# DFTT.net
KiCad netlist of a schematic drawn in EAGLE
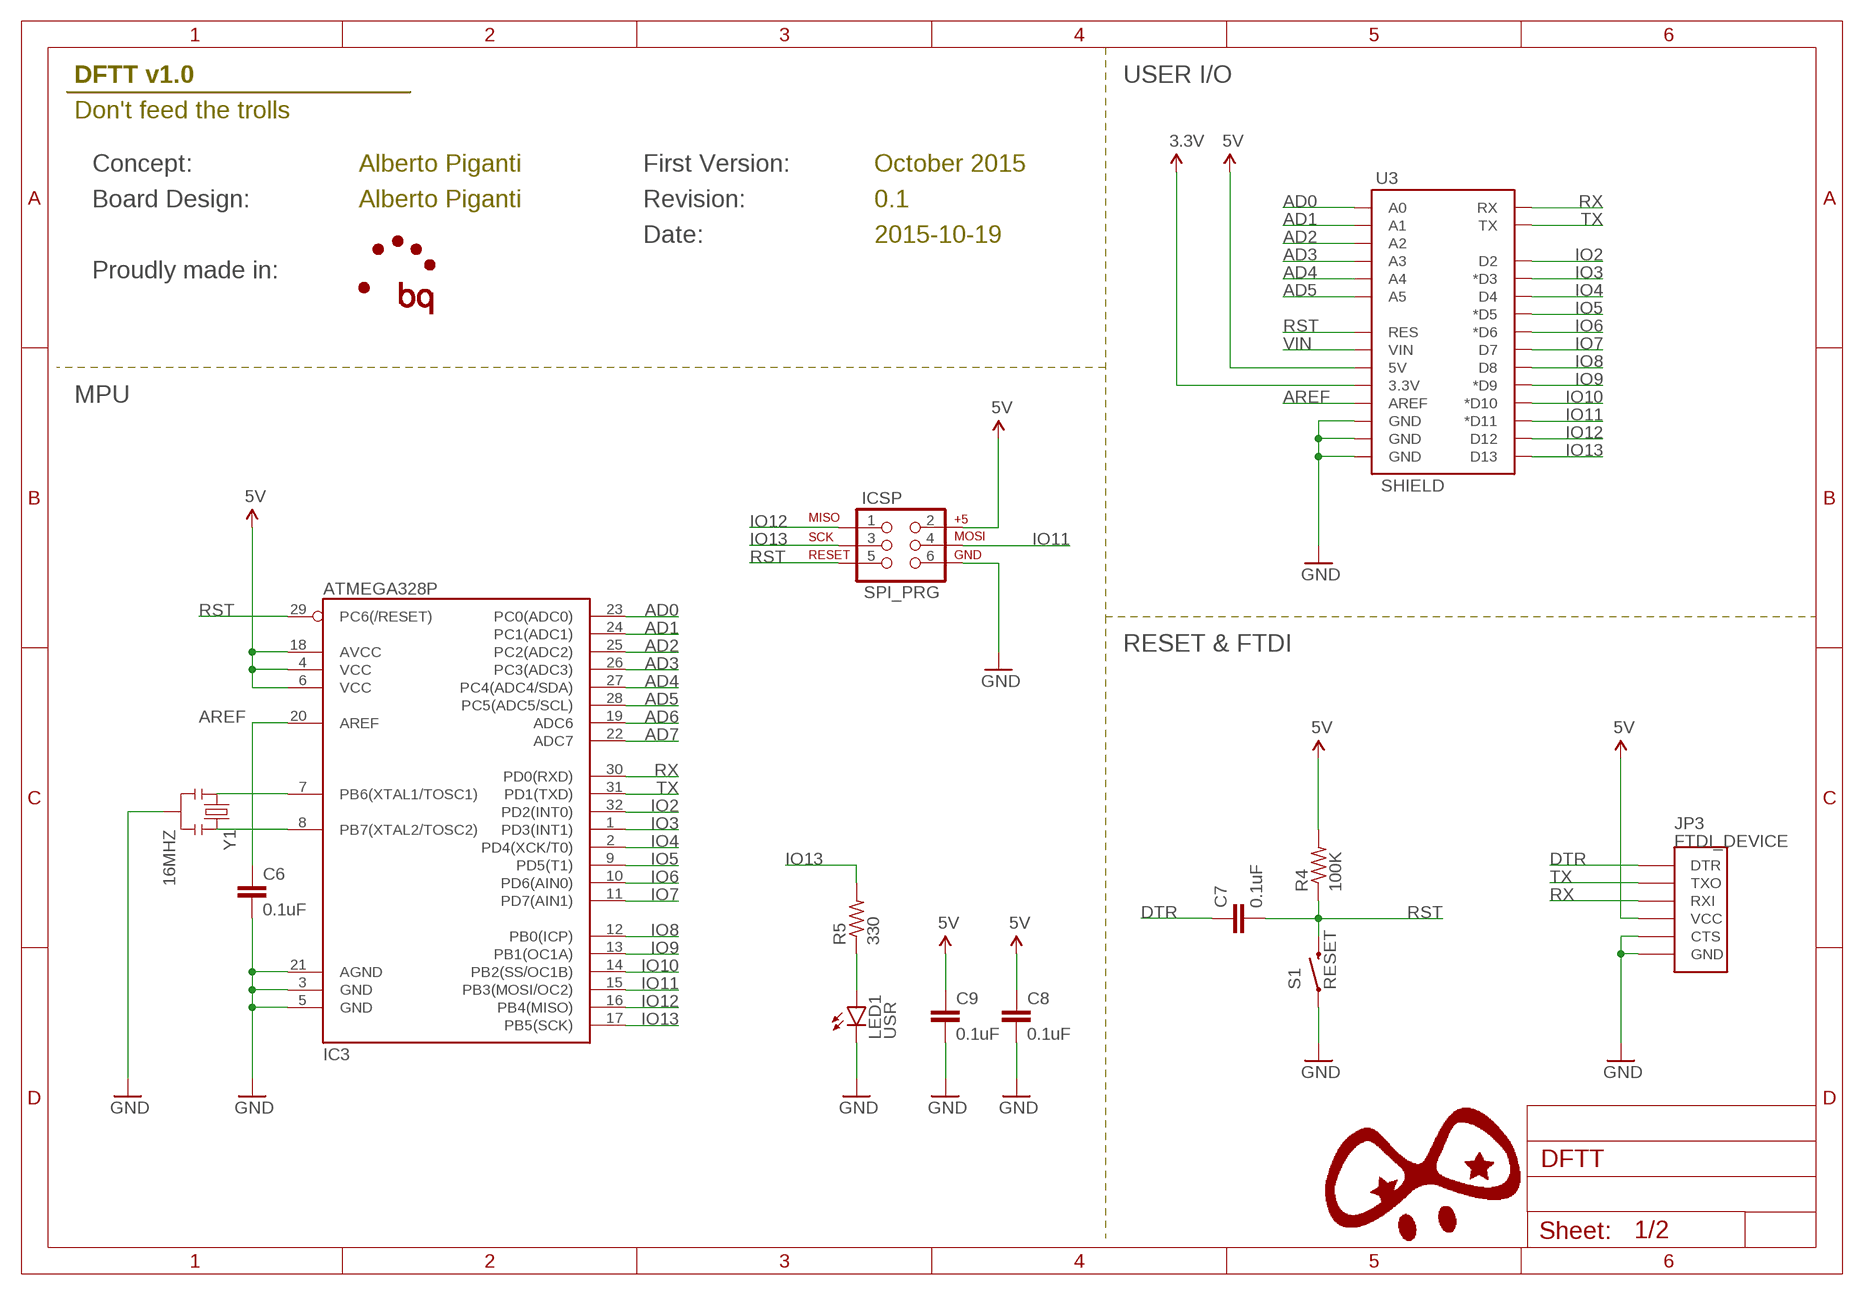
[diagram p0: schematic, sheet 1]
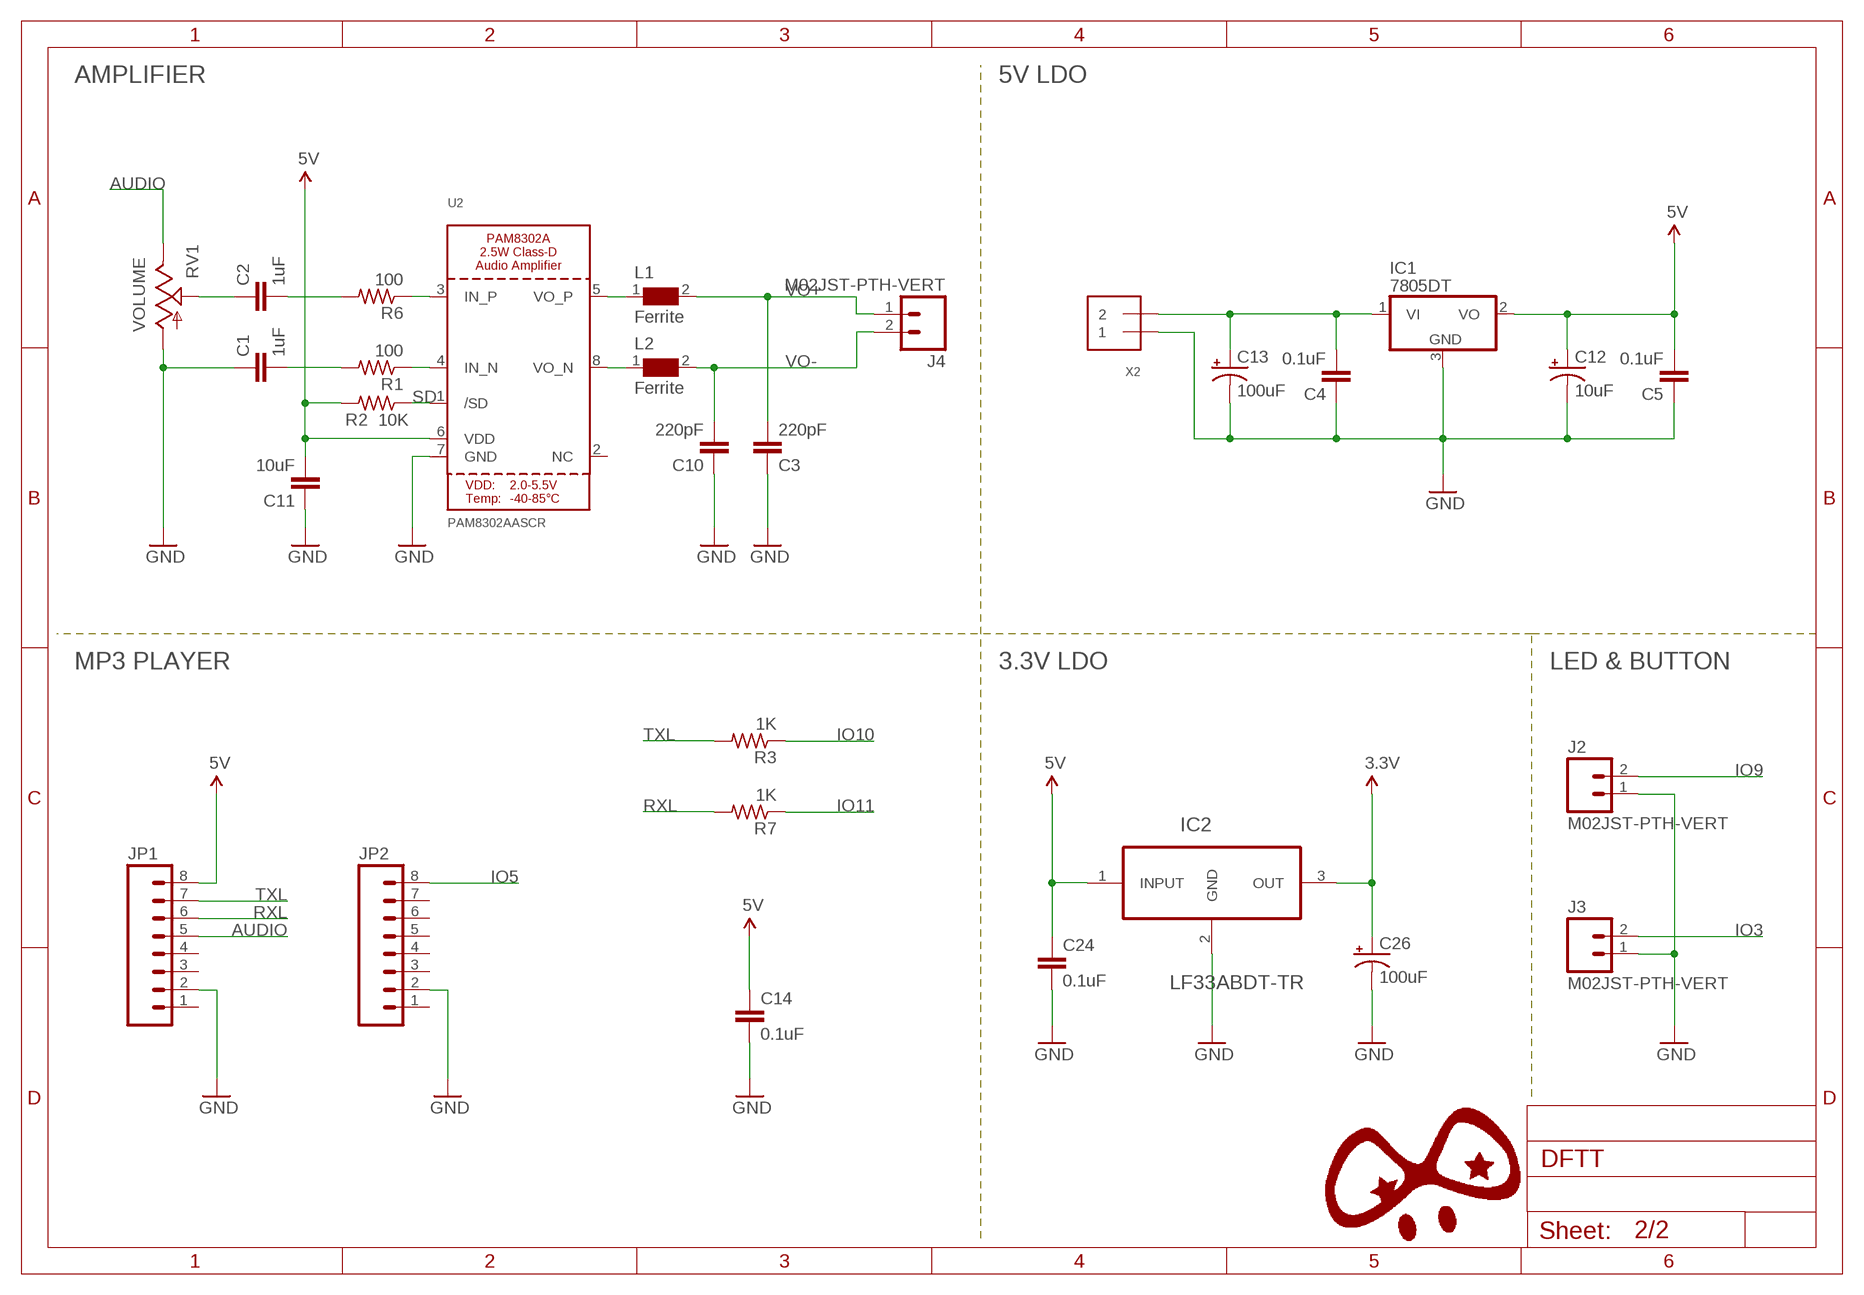
[diagram p1: schematic, sheet 2]

(export (version "E")
  (design (tool "Eeschema 10.0.6"))
  (components
    (comp (ref "C6")
      (value "0.1uF")
      (footprint "eagle-import:C0603")
      (libsource (lib "eagle-import") (part "C-EUC0603"))
    )
    (comp (ref "C7")
      (value "0.1uF")
      (footprint "eagle-import:C0603")
      (libsource (lib "eagle-import") (part "C-EUC0603"))
    )
    (comp (ref "C8")
      (value "0.1uF")
      (footprint "eagle-import:C0603")
      (libsource (lib "eagle-import") (part "C-EUC0603"))
    )
    (comp (ref "C9")
      (value "0.1uF")
      (footprint "eagle-import:C0603")
      (libsource (lib "eagle-import") (part "C-EUC0603"))
    )
    (comp (ref "IC3")
      (value "ATMEGA328P")
      (footprint "eagle-import:TQFP32-08")
      (libsource (lib "eagle-import") (part "ATMEGA328_SMT"))
    )
    (comp (ref "ICSP")
      (value "SPI_PRG")
      (footprint "eagle-import:2X3-NS")
      (libsource (lib "eagle-import") (part "AVR_SPI_PRG_6NS"))
    )
    (comp (ref "JP3")
      (value "FTDI_DEVICE")
      (footprint "eagle-import:FTDI_DEVICE_SIDE")
      (libsource (lib "eagle-import") (part "FTDI_DEVICE"))
    )
    (comp (ref "LED1")
      (value "USR")
      (footprint "eagle-import:LED-0603")
      (libsource (lib "eagle-import") (part "LED0603"))
    )
    (comp (ref "R4")
      (value "100K")
      (footprint "eagle-import:R0603")
      (libsource (lib "eagle-import") (part "R-US_R0603"))
    )
    (comp (ref "R5")
      (value "330")
      (footprint "eagle-import:R0603")
      (libsource (lib "eagle-import") (part "R-US_R0603"))
    )
    (comp (ref "S1")
      (value "RESET")
      (footprint "eagle-import:TACTILE-SWITCH-1101NE")
      (libsource (lib "eagle-import") (part "SWITCH-MOMENTARY-2SMD-1101NE"))
    )
    (comp (ref "U3")
      (value "SHIELD")
      (footprint "eagle-import:DUEMILANOVE_VIAS")
      (libsource (lib "eagle-import") (part "ARDUINO_SHIELDNO_SILK"))
    )
    (comp (ref "Y1")
      (value "16MHZ")
      (footprint "eagle-import:RESONATOR-SMD")
      (libsource (lib "eagle-import") (part "RESONATOR16MHZ"))
    )
    (comp (ref "C1")
      (value "1uF")
      (footprint "eagle-import:C0603")
      (libsource (lib "eagle-import") (part "C-EUC0603"))
    )
    (comp (ref "C2")
      (value "1uF")
      (footprint "eagle-import:C0603")
      (libsource (lib "eagle-import") (part "C-EUC0603"))
    )
    (comp (ref "C3")
      (value "220pF")
      (footprint "eagle-import:C0603")
      (libsource (lib "eagle-import") (part "C-EUC0603"))
    )
    (comp (ref "C4")
      (value "0.1uF")
      (footprint "eagle-import:C0603")
      (libsource (lib "eagle-import") (part "C-EUC0603"))
    )
    (comp (ref "C5")
      (value "0.1uF")
      (footprint "eagle-import:C0603")
      (libsource (lib "eagle-import") (part "C-EUC0603"))
    )
    (comp (ref "C10")
      (value "220pF")
      (footprint "eagle-import:C0603")
      (libsource (lib "eagle-import") (part "C-EUC0603"))
    )
    (comp (ref "C11")
      (value "10uF")
      (footprint "eagle-import:C0603")
      (libsource (lib "eagle-import") (part "C-EUC0603"))
    )
    (comp (ref "C12")
      (value "10uF")
      (footprint "eagle-import:PANASONIC_D")
      (libsource (lib "eagle-import") (part "CAP_POLD"))
    )
    (comp (ref "C13")
      (value "100uF")
      (footprint "eagle-import:PANASONIC_D")
      (libsource (lib "eagle-import") (part "CAP_POLD"))
    )
    (comp (ref "C14")
      (value "0.1uF")
      (footprint "eagle-import:1210")
      (libsource (lib "eagle-import") (part "CAP1210"))
    )
    (comp (ref "C24")
      (value "0.1uF")
      (footprint "eagle-import:1210")
      (libsource (lib "eagle-import") (part "CAP1210"))
    )
    (comp (ref "C26")
      (value "100uF")
      (footprint "eagle-import:PANASONIC_D")
      (libsource (lib "eagle-import") (part "CAP_POLD"))
    )
    (comp (ref "IC1")
      (value "7805DT")
      (footprint "eagle-import:TO252")
      (libsource (lib "eagle-import") (part "78DT05"))
    )
    (comp (ref "IC2")
      (value "LF33ABDT-TR")
      (footprint "eagle-import:TO228P972X240-3N")
      (libsource (lib "eagle-import") (part "LF33ABDT-TR"))
    )
    (comp (ref "J2")
      (value "M02JST-PTH-VERT")
      (footprint "eagle-import:JST-2-PTH-VERT")
      (libsource (lib "eagle-import") (part "M02JST-PTH-VERT"))
    )
    (comp (ref "J3")
      (value "M02JST-PTH-VERT")
      (footprint "eagle-import:JST-2-PTH-VERT")
      (libsource (lib "eagle-import") (part "M02JST-PTH-VERT"))
    )
    (comp (ref "J4")
      (value "M02JST-PTH-VERT")
      (footprint "eagle-import:JST-2-PTH-VERT")
      (libsource (lib "eagle-import") (part "M02JST-PTH-VERT"))
    )
    (comp (ref "JP1")
      (value "M08LOCK")
      (footprint "eagle-import:1X08_LOCK")
      (libsource (lib "eagle-import") (part "M08LOCK"))
    )
    (comp (ref "JP2")
      (value "M08LOCK")
      (footprint "eagle-import:1X08_LOCK")
      (libsource (lib "eagle-import") (part "M08LOCK"))
    )
    (comp (ref "L1")
      (value "Ferrite")
      (footprint "eagle-import:0603")
      (fields (field (name "MPN") "74279261"))
      (libsource (lib "eagle-import") (part "FERRITE_0603-74279261"))
    )
    (comp (ref "L2")
      (value "Ferrite")
      (footprint "eagle-import:0603")
      (fields (field (name "MPN") "74279261"))
      (libsource (lib "eagle-import") (part "FERRITE_0603-74279261"))
    )
    (comp (ref "R1")
      (value "100")
      (footprint "eagle-import:R0603")
      (libsource (lib "eagle-import") (part "R-US_R0603"))
    )
    (comp (ref "R2")
      (value "10K")
      (footprint "eagle-import:R0603")
      (libsource (lib "eagle-import") (part "R-US_R0603"))
    )
    (comp (ref "R3")
      (value "1K")
      (footprint "eagle-import:R0603")
      (libsource (lib "eagle-import") (part "R-US_R0603"))
    )
    (comp (ref "R6")
      (value "100")
      (footprint "eagle-import:R0603")
      (libsource (lib "eagle-import") (part "R-US_R0603"))
    )
    (comp (ref "R7")
      (value "1K")
      (footprint "eagle-import:R0603")
      (libsource (lib "eagle-import") (part "R-US_R0603"))
    )
    (comp (ref "RV1")
      (value "VOLUME")
      (footprint "eagle-import:TRIM_POT")
      (libsource (lib "eagle-import") (part "POTTRIM"))
    )
    (comp (ref "U2")
      (value "PAM8302AASCR")
      (footprint "eagle-import:MSOP8_0.65MM")
      (libsource (lib "eagle-import") (part "AUDIOAMP_PAM8302A"))
    )
    (comp (ref "X2")
      (value "TERMBLOCK_1X2")
      (footprint "eagle-import:TERMBLOCK_1X2-3.5MM")
      (libsource (lib "eagle-import") (part "TERMBLOCK_1X2"))
    )
  )
  (nets
    (net (code "1") (name "3.3V") (class "Default")
      (node (ref "C26") (pin "+") (pinfunction "+_+") (pintype "passive"))
      (node (ref "IC2") (pin "3") (pinfunction "OUT_3") (pintype "output"))
      (node (ref "U3") (pin "3.3V") (pinfunction "3.3V_3.3V") (pintype "bidirectional"))
    )
    (net (code "2") (name "5V") (class "Default")
      (node (ref "C11") (pin "2") (pinfunction "2_2") (pintype "passive"))
      (node (ref "C12") (pin "+") (pinfunction "+_+") (pintype "passive"))
      (node (ref "C14") (pin "1") (pinfunction "1_1") (pintype "passive"))
      (node (ref "C24") (pin "1") (pinfunction "1_1") (pintype "passive"))
      (node (ref "C5") (pin "2") (pinfunction "2_2") (pintype "passive"))
      (node (ref "C8") (pin "1") (pinfunction "1_1") (pintype "passive"))
      (node (ref "C9") (pin "1") (pinfunction "1_1") (pintype "passive"))
      (node (ref "IC1") (pin "2") (pinfunction "VO_2") (pintype "passive"))
      (node (ref "IC2") (pin "1") (pinfunction "INPUT_1") (pintype "input"))
      (node (ref "IC3") (pin "18") (pinfunction "AVCC_18") (pintype "bidirectional"))
      (node (ref "IC3") (pin "4") (pinfunction "VCC_4") (pintype "bidirectional"))
      (node (ref "IC3") (pin "6") (pinfunction "VCC_6") (pintype "bidirectional"))
      (node (ref "ICSP") (pin "2") (pinfunction "2_2") (pintype "passive"))
      (node (ref "JP1") (pin "8") (pinfunction "8_8") (pintype "passive"))
      (node (ref "JP3") (pin "P$4") (pinfunction "VCC_P$4") (pintype "bidirectional"))
      (node (ref "R2") (pin "2") (pinfunction "2_2") (pintype "passive"))
      (node (ref "R4") (pin "2") (pinfunction "2_2") (pintype "passive"))
      (node (ref "U2") (pin "6") (pinfunction "VDD_6") (pintype "power_in"))
      (node (ref "U3") (pin "5V") (pinfunction "5V_5V") (pintype "bidirectional"))
    )
    (net (code "3") (name "AD0") (class "Default")
      (node (ref "IC3") (pin "23") (pinfunction "PC0(ADC0)_23") (pintype "bidirectional"))
      (node (ref "U3") (pin "A0") (pinfunction "A0_A0") (pintype "bidirectional"))
    )
    (net (code "4") (name "AD1") (class "Default")
      (node (ref "IC3") (pin "24") (pinfunction "PC1(ADC1)_24") (pintype "bidirectional"))
      (node (ref "U3") (pin "A1") (pinfunction "A1_A1") (pintype "bidirectional"))
    )
    (net (code "5") (name "AD2") (class "Default")
      (node (ref "IC3") (pin "25") (pinfunction "PC2(ADC2)_25") (pintype "bidirectional"))
      (node (ref "U3") (pin "A2") (pinfunction "A2_A2") (pintype "bidirectional"))
    )
    (net (code "6") (name "AD3") (class "Default")
      (node (ref "IC3") (pin "26") (pinfunction "PC3(ADC3)_26") (pintype "bidirectional"))
      (node (ref "U3") (pin "A3") (pinfunction "A3_A3") (pintype "bidirectional"))
    )
    (net (code "7") (name "AD4") (class "Default")
      (node (ref "IC3") (pin "27") (pinfunction "PC4(ADC4/SDA)_27") (pintype "bidirectional"))
      (node (ref "U3") (pin "A4") (pinfunction "A4_A4") (pintype "bidirectional"))
    )
    (net (code "8") (name "AD5") (class "Default")
      (node (ref "IC3") (pin "28") (pinfunction "PC5(ADC5/SCL)_28") (pintype "bidirectional"))
      (node (ref "U3") (pin "A5") (pinfunction "A5_A5") (pintype "bidirectional"))
    )
    (net (code "9") (name "AD6") (class "Default")
      (node (ref "IC3") (pin "19") (pinfunction "ADC6_19") (pintype "bidirectional"))
    )
    (net (code "10") (name "AD7") (class "Default")
      (node (ref "IC3") (pin "22") (pinfunction "ADC7_22") (pintype "bidirectional"))
    )
    (net (code "11") (name "AREF") (class "Default")
      (node (ref "C6") (pin "1") (pinfunction "1_1") (pintype "passive"))
      (node (ref "IC3") (pin "20") (pinfunction "AREF_20") (pintype "bidirectional"))
      (node (ref "U3") (pin "AREF") (pinfunction "AREF_AREF") (pintype "bidirectional"))
    )
    (net (code "12") (name "AUDIO") (class "Default")
      (node (ref "JP1") (pin "5") (pinfunction "5_5") (pintype "passive"))
      (node (ref "RV1") (pin "2") (pinfunction "E_2") (pintype "passive"))
    )
    (net (code "13") (name "DTR") (class "Default")
      (node (ref "C7") (pin "1") (pinfunction "1_1") (pintype "passive"))
      (node (ref "JP3") (pin "P$1") (pinfunction "DTR_P$1") (pintype "bidirectional"))
    )
    (net (code "14") (name "GND") (class "Default")
      (node (ref "C1") (pin "1") (pinfunction "1_1") (pintype "passive"))
      (node (ref "C10") (pin "1") (pinfunction "1_1") (pintype "passive"))
      (node (ref "C11") (pin "1") (pinfunction "1_1") (pintype "passive"))
      (node (ref "C12") (pin "-") (pinfunction "-_-") (pintype "passive"))
      (node (ref "C13") (pin "-") (pinfunction "-_-") (pintype "passive"))
      (node (ref "C14") (pin "2") (pinfunction "2_2") (pintype "passive"))
      (node (ref "C24") (pin "2") (pinfunction "2_2") (pintype "passive"))
      (node (ref "C26") (pin "-") (pinfunction "-_-") (pintype "passive"))
      (node (ref "C3") (pin "1") (pinfunction "1_1") (pintype "passive"))
      (node (ref "C4") (pin "1") (pinfunction "1_1") (pintype "passive"))
      (node (ref "C5") (pin "1") (pinfunction "1_1") (pintype "passive"))
      (node (ref "C6") (pin "2") (pinfunction "2_2") (pintype "passive"))
      (node (ref "C8") (pin "2") (pinfunction "2_2") (pintype "passive"))
      (node (ref "C9") (pin "2") (pinfunction "2_2") (pintype "passive"))
      (node (ref "IC1") (pin "3") (pinfunction "GND_3") (pintype "passive"))
      (node (ref "IC2") (pin "2") (pinfunction "GND_2") (pintype "passive"))
      (node (ref "IC3") (pin "21") (pinfunction "AGND_21") (pintype "bidirectional"))
      (node (ref "IC3") (pin "3") (pinfunction "GND_3") (pintype "bidirectional"))
      (node (ref "IC3") (pin "5") (pinfunction "GND_5") (pintype "bidirectional"))
      (node (ref "ICSP") (pin "6") (pinfunction "6_6") (pintype "passive"))
      (node (ref "J2") (pin "1") (pinfunction "1_1") (pintype "passive"))
      (node (ref "J3") (pin "1") (pinfunction "1_1") (pintype "passive"))
      (node (ref "JP1") (pin "2") (pinfunction "2_2") (pintype "passive"))
      (node (ref "JP2") (pin "2") (pinfunction "2_2") (pintype "passive"))
      (node (ref "JP3") (pin "P$5") (pinfunction "CTS_P$5") (pintype "bidirectional"))
      (node (ref "JP3") (pin "P$6") (pinfunction "GND_P$6") (pintype "bidirectional"))
      (node (ref "LED1") (pin "C") (pinfunction "C_C") (pintype "passive"))
      (node (ref "RV1") (pin "3") (pinfunction "A_3") (pintype "passive"))
      (node (ref "S1") (pin "1") (pinfunction "1_1") (pintype "passive"))
      (node (ref "U2") (pin "7") (pinfunction "GND_7") (pintype "power_in"))
      (node (ref "U3") (pin "GND@0") (pinfunction "GND_GND@0") (pintype "bidirectional"))
      (node (ref "U3") (pin "GND@1") (pinfunction "GND_GND@1") (pintype "bidirectional"))
      (node (ref "U3") (pin "GND@2") (pinfunction "GND_GND@2") (pintype "bidirectional"))
      (node (ref "X2") (pin "1") (pinfunction "1_1") (pintype "passive"))
      (node (ref "Y1") (pin "2") (pinfunction "2_2") (pintype "passive"))
    )
    (net (code "15") (name "IO2") (class "Default")
      (node (ref "IC3") (pin "32") (pinfunction "PD2(INT0)_32") (pintype "bidirectional"))
      (node (ref "U3") (pin "D2") (pinfunction "D2_D2") (pintype "bidirectional"))
    )
    (net (code "16") (name "IO3") (class "Default")
      (node (ref "IC3") (pin "1") (pinfunction "PD3(INT1)_1") (pintype "bidirectional"))
      (node (ref "J3") (pin "2") (pinfunction "2_2") (pintype "passive"))
      (node (ref "U3") (pin "D3") (pinfunction "*D3_D3") (pintype "bidirectional"))
    )
    (net (code "17") (name "IO4") (class "Default")
      (node (ref "IC3") (pin "2") (pinfunction "PD4(XCK/T0)_2") (pintype "bidirectional"))
      (node (ref "U3") (pin "D4") (pinfunction "D4_D4") (pintype "bidirectional"))
    )
    (net (code "18") (name "IO5") (class "Default")
      (node (ref "IC3") (pin "9") (pinfunction "PD5(T1)_9") (pintype "bidirectional"))
      (node (ref "JP2") (pin "8") (pinfunction "8_8") (pintype "passive"))
      (node (ref "U3") (pin "D5") (pinfunction "*D5_D5") (pintype "bidirectional"))
    )
    (net (code "19") (name "IO6") (class "Default")
      (node (ref "IC3") (pin "10") (pinfunction "PD6(AIN0)_10") (pintype "bidirectional"))
      (node (ref "U3") (pin "D6") (pinfunction "*D6_D6") (pintype "bidirectional"))
    )
    (net (code "20") (name "IO7") (class "Default")
      (node (ref "IC3") (pin "11") (pinfunction "PD7(AIN1)_11") (pintype "bidirectional"))
      (node (ref "U3") (pin "D7") (pinfunction "D7_D7") (pintype "bidirectional"))
    )
    (net (code "21") (name "IO8") (class "Default")
      (node (ref "IC3") (pin "12") (pinfunction "PB0(ICP)_12") (pintype "bidirectional"))
      (node (ref "U3") (pin "D8") (pinfunction "D8_D8") (pintype "bidirectional"))
    )
    (net (code "22") (name "IO9") (class "Default")
      (node (ref "IC3") (pin "13") (pinfunction "PB1(OC1A)_13") (pintype "bidirectional"))
      (node (ref "J2") (pin "2") (pinfunction "2_2") (pintype "passive"))
      (node (ref "U3") (pin "D9") (pinfunction "*D9_D9") (pintype "bidirectional"))
    )
    (net (code "23") (name "IO10") (class "Default")
      (node (ref "IC3") (pin "14") (pinfunction "PB2(SS/OC1B)_14") (pintype "bidirectional"))
      (node (ref "R3") (pin "1") (pinfunction "1_1") (pintype "passive"))
      (node (ref "U3") (pin "D10") (pinfunction "*D10_D10") (pintype "bidirectional"))
    )
    (net (code "24") (name "IO11") (class "Default")
      (node (ref "IC3") (pin "15") (pinfunction "PB3(MOSI/OC2)_15") (pintype "bidirectional"))
      (node (ref "ICSP") (pin "4") (pinfunction "4_4") (pintype "passive"))
      (node (ref "R7") (pin "1") (pinfunction "1_1") (pintype "passive"))
      (node (ref "U3") (pin "D11") (pinfunction "*D11_D11") (pintype "bidirectional"))
    )
    (net (code "25") (name "IO12") (class "Default")
      (node (ref "IC3") (pin "16") (pinfunction "PB4(MISO)_16") (pintype "bidirectional"))
      (node (ref "ICSP") (pin "1") (pinfunction "1_1") (pintype "passive"))
      (node (ref "U3") (pin "D12") (pinfunction "D12_D12") (pintype "bidirectional"))
    )
    (net (code "26") (name "IO13") (class "Default")
      (node (ref "IC3") (pin "17") (pinfunction "PB5(SCK)_17") (pintype "bidirectional"))
      (node (ref "ICSP") (pin "3") (pinfunction "3_3") (pintype "passive"))
      (node (ref "R5") (pin "2") (pinfunction "2_2") (pintype "passive"))
      (node (ref "U3") (pin "D13") (pinfunction "D13_D13") (pintype "bidirectional"))
    )
    (net (code "27") (name "Net-(C1-Pad2)") (class "Default")
      (node (ref "C1") (pin "2") (pinfunction "2_2") (pintype "passive"))
      (node (ref "R1") (pin "2") (pinfunction "2_2") (pintype "passive"))
    )
    (net (code "28") (name "Net-(C2-Pad2)") (class "Default")
      (node (ref "C2") (pin "2") (pinfunction "2_2") (pintype "passive"))
      (node (ref "R6") (pin "2") (pinfunction "2_2") (pintype "passive"))
    )
    (net (code "29") (name "Net-(IC1-VI)") (class "Default")
      (node (ref "C13") (pin "+") (pinfunction "+_+") (pintype "passive"))
      (node (ref "C4") (pin "2") (pinfunction "2_2") (pintype "passive"))
      (node (ref "IC1") (pin "1") (pinfunction "VI_1") (pintype "input"))
      (node (ref "X2") (pin "2") (pinfunction "2_2") (pintype "passive"))
    )
    (net (code "30") (name "Net-(IC3-PB6(XTAL1{slash}TOSC1))") (class "Default")
      (node (ref "IC3") (pin "7") (pinfunction "PB6(XTAL1/TOSC1)_7") (pintype "bidirectional"))
      (node (ref "Y1") (pin "1") (pinfunction "1_1") (pintype "passive"))
    )
    (net (code "31") (name "Net-(IC3-PB7(XTAL2{slash}TOSC2))") (class "Default")
      (node (ref "IC3") (pin "8") (pinfunction "PB7(XTAL2/TOSC2)_8") (pintype "bidirectional"))
      (node (ref "Y1") (pin "3") (pinfunction "3_3") (pintype "passive"))
    )
    (net (code "32") (name "Net-(LED1-PadA)") (class "Default")
      (node (ref "LED1") (pin "A") (pinfunction "A_A") (pintype "passive"))
      (node (ref "R5") (pin "1") (pinfunction "1_1") (pintype "passive"))
    )
    (net (code "33") (name "Net-(RV1-S)") (class "Default")
      (node (ref "C2") (pin "1") (pinfunction "1_1") (pintype "passive"))
      (node (ref "RV1") (pin "1") (pinfunction "S_1") (pintype "passive"))
    )
    (net (code "34") (name "Net-(U2-IN_N)") (class "Default")
      (node (ref "R1") (pin "1") (pinfunction "1_1") (pintype "passive"))
      (node (ref "U2") (pin "4") (pinfunction "IN_N_4") (pintype "input"))
    )
    (net (code "35") (name "Net-(U2-IN_P)") (class "Default")
      (node (ref "R6") (pin "1") (pinfunction "1_1") (pintype "passive"))
      (node (ref "U2") (pin "3") (pinfunction "IN_P_3") (pintype "input"))
    )
    (net (code "36") (name "Net-(U2-VO_N)") (class "Default")
      (node (ref "L2") (pin "1") (pinfunction "1_1") (pintype "passive"))
      (node (ref "U2") (pin "8") (pinfunction "VO_N_8") (pintype "output"))
    )
    (net (code "37") (name "Net-(U2-VO_P)") (class "Default")
      (node (ref "L1") (pin "1") (pinfunction "1_1") (pintype "passive"))
      (node (ref "U2") (pin "5") (pinfunction "VO_P_5") (pintype "output"))
    )
    (net (code "38") (name "RST") (class "Default")
      (node (ref "C7") (pin "2") (pinfunction "2_2") (pintype "passive"))
      (node (ref "IC3") (pin "29") (pinfunction "PC6(/RESET)_29") (pintype "bidirectional"))
      (node (ref "ICSP") (pin "5") (pinfunction "5_5") (pintype "passive"))
      (node (ref "R4") (pin "1") (pinfunction "1_1") (pintype "passive"))
      (node (ref "S1") (pin "2") (pinfunction "2_2") (pintype "passive"))
      (node (ref "U3") (pin "RES") (pinfunction "RES_RES") (pintype "bidirectional"))
    )
    (net (code "39") (name "RX") (class "Default")
      (node (ref "IC3") (pin "30") (pinfunction "PD0(RXD)_30") (pintype "bidirectional"))
      (node (ref "JP3") (pin "P$3") (pinfunction "RXI_P$3") (pintype "bidirectional"))
      (node (ref "U3") (pin "RX") (pinfunction "RX_RX") (pintype "bidirectional"))
    )
    (net (code "40") (name "RXL") (class "Default")
      (node (ref "JP1") (pin "6") (pinfunction "6_6") (pintype "passive"))
      (node (ref "R7") (pin "2") (pinfunction "2_2") (pintype "passive"))
    )
    (net (code "41") (name "SD") (class "Default")
      (node (ref "R2") (pin "1") (pinfunction "1_1") (pintype "passive"))
      (node (ref "U2") (pin "1") (pinfunction "/SD_1") (pintype "input"))
    )
    (net (code "42") (name "TX") (class "Default")
      (node (ref "IC3") (pin "31") (pinfunction "PD1(TXD)_31") (pintype "bidirectional"))
      (node (ref "JP3") (pin "P$2") (pinfunction "TXO_P$2") (pintype "bidirectional"))
      (node (ref "U3") (pin "TX") (pinfunction "TX_TX") (pintype "bidirectional"))
    )
    (net (code "43") (name "TXL") (class "Default")
      (node (ref "JP1") (pin "7") (pinfunction "7_7") (pintype "passive"))
      (node (ref "R3") (pin "2") (pinfunction "2_2") (pintype "passive"))
    )
    (net (code "44") (name "VIN") (class "Default")
      (node (ref "U3") (pin "VIN") (pinfunction "VIN_VIN") (pintype "bidirectional"))
    )
    (net (code "45") (name "VO+") (class "Default")
      (node (ref "C3") (pin "2") (pinfunction "2_2") (pintype "passive"))
      (node (ref "J4") (pin "1") (pinfunction "1_1") (pintype "passive"))
      (node (ref "L1") (pin "2") (pinfunction "2_2") (pintype "passive"))
    )
    (net (code "46") (name "VO-") (class "Default")
      (node (ref "C10") (pin "2") (pinfunction "2_2") (pintype "passive"))
      (node (ref "J4") (pin "2") (pinfunction "2_2") (pintype "passive"))
      (node (ref "L2") (pin "2") (pinfunction "2_2") (pintype "passive"))
    )
    (net (code "47") (name "unconnected-(JP1-Pad1)") (class "Default")
      (node (ref "JP1") (pin "1") (pinfunction "1_1") (pintype "passive"))
    )
    (net (code "48") (name "unconnected-(JP1-Pad3)") (class "Default")
      (node (ref "JP1") (pin "3") (pinfunction "3_3") (pintype "passive"))
    )
    (net (code "49") (name "unconnected-(JP1-Pad4)") (class "Default")
      (node (ref "JP1") (pin "4") (pinfunction "4_4") (pintype "passive"))
    )
    (net (code "50") (name "unconnected-(JP2-Pad1)") (class "Default")
      (node (ref "JP2") (pin "1") (pinfunction "1_1") (pintype "passive"))
    )
    (net (code "51") (name "unconnected-(JP2-Pad3)") (class "Default")
      (node (ref "JP2") (pin "3") (pinfunction "3_3") (pintype "passive"))
    )
    (net (code "52") (name "unconnected-(JP2-Pad4)") (class "Default")
      (node (ref "JP2") (pin "4") (pinfunction "4_4") (pintype "passive"))
    )
    (net (code "53") (name "unconnected-(JP2-Pad5)") (class "Default")
      (node (ref "JP2") (pin "5") (pinfunction "5_5") (pintype "passive"))
    )
    (net (code "54") (name "unconnected-(JP2-Pad6)") (class "Default")
      (node (ref "JP2") (pin "6") (pinfunction "6_6") (pintype "passive"))
    )
    (net (code "55") (name "unconnected-(JP2-Pad7)") (class "Default")
      (node (ref "JP2") (pin "7") (pinfunction "7_7") (pintype "passive"))
    )
    (net (code "56") (name "unconnected-(U2-NC-Pad2)") (class "Default")
      (node (ref "U2") (pin "2") (pinfunction "NC_2") (pintype "no_connect"))
    )
  )
)
